# nixiRemoteControlReceiver.net
KiCad netlist of a schematic drawn in EAGLE
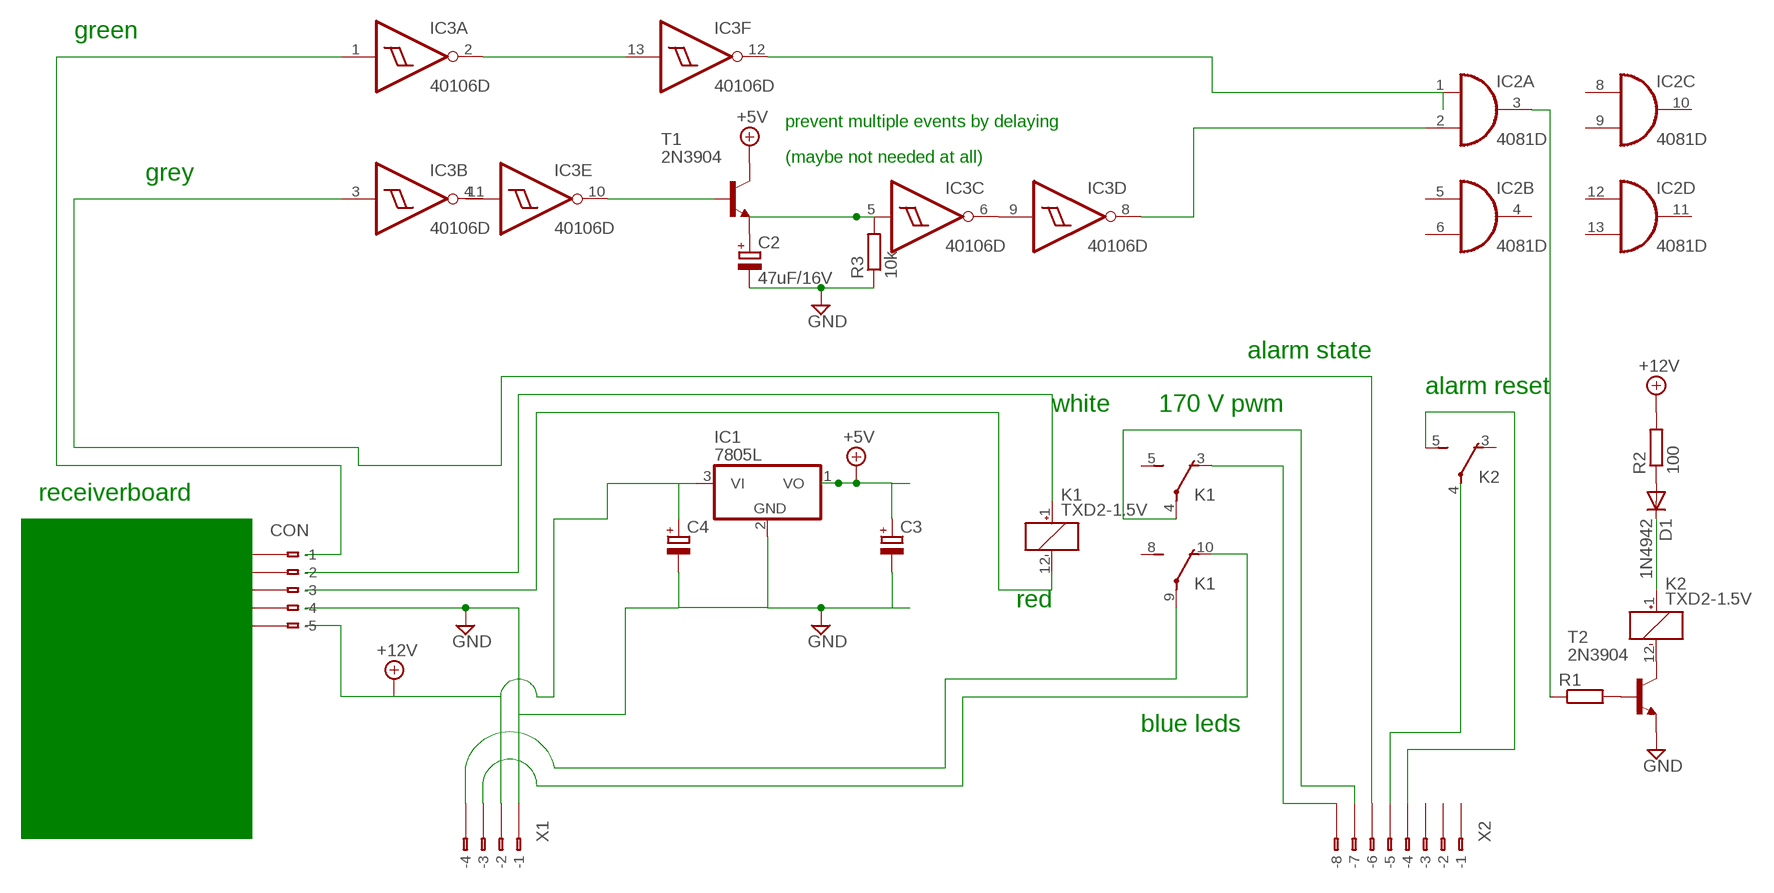
[diagram p0: schematic, sheet 1]

(export (version "E")
  (design (tool "Eeschema 10.0.6"))
  (components
    (comp (ref "C2")
      (value "47uF/16V")
      (footprint "eagle-import:EB20D")
      (libsource (lib "eagle-import") (part "CPOL-EUE10-20"))
    )
    (comp (ref "C3")
      (value "CPOL-EUE10-20")
      (footprint "eagle-import:EB20D")
      (libsource (lib "eagle-import") (part "CPOL-EUE10-20"))
    )
    (comp (ref "C4")
      (value "CPOL-EUE10-20")
      (footprint "eagle-import:EB20D")
      (libsource (lib "eagle-import") (part "CPOL-EUE10-20"))
    )
    (comp (ref "CON")
      (value "233-105")
      (footprint "eagle-import:233-105")
      (libsource (lib "eagle-import") (part "233-105"))
    )
    (comp (ref "D1")
      (value "1N4942")
      (footprint "eagle-import:DO41-10")
      (libsource (lib "eagle-import") (part "1N4942"))
    )
    (comp (ref "IC1")
      (value "7805L")
      (footprint "eagle-import:TO92")
      (libsource (lib "eagle-import") (part "78L05"))
    )
    (comp (ref "IC2")
      (value "4081D")
      (footprint "eagle-import:SO14")
      (libsource (lib "eagle-import") (part "4081D"))
    )
    (comp (ref "IC3")
      (value "40106D")
      (footprint "eagle-import:SO14")
      (libsource (lib "eagle-import") (part "40106D"))
    )
    (comp (ref "K1")
      (value "TXD2-1.5V")
      (footprint "eagle-import:TXD2")
      (libsource (lib "eagle-import") (part "TX?-D21.5V"))
    )
    (comp (ref "K2")
      (value "TXD2-1.5V")
      (footprint "eagle-import:TXD2")
      (libsource (lib "eagle-import") (part "TX?-D21.5V"))
    )
    (comp (ref "R1")
      (value "R-EU_0411/15")
      (footprint "eagle-import:0411_15")
      (libsource (lib "eagle-import") (part "R-EU_0411/15"))
    )
    (comp (ref "R2")
      (value "100")
      (footprint "eagle-import:0411_15")
      (libsource (lib "eagle-import") (part "R-EU_0411/15"))
    )
    (comp (ref "R3")
      (value "10k")
      (footprint "eagle-import:0411_15")
      (libsource (lib "eagle-import") (part "R-EU_0411/15"))
    )
    (comp (ref "T1")
      (value "2N3904")
      (footprint "eagle-import:TO92")
      (libsource (lib "eagle-import") (part "2N3904"))
    )
    (comp (ref "T2")
      (value "2N3904")
      (footprint "eagle-import:TO92")
      (libsource (lib "eagle-import") (part "2N3904"))
    )
    (comp (ref "X1")
      (value "233-104")
      (footprint "eagle-import:233-104")
      (libsource (lib "eagle-import") (part "233-104"))
    )
    (comp (ref "X2")
      (value "233-108")
      (footprint "eagle-import:233-108")
      (libsource (lib "eagle-import") (part "233-108"))
    )
  )
  (nets
    (net (code "1") (name "+5V") (class "Default")
      (node (ref "C3") (pin "+") (pinfunction "+_+") (pintype "passive"))
      (node (ref "IC1") (pin "1") (pinfunction "VO_1") (pintype "passive"))
      (node (ref "T1") (pin "1") (pinfunction "C_1") (pintype "passive"))
    )
    (net (code "2") (name "+12V") (class "Default")
      (node (ref "C4") (pin "+") (pinfunction "+_+") (pintype "passive"))
      (node (ref "IC1") (pin "3") (pinfunction "VI_3") (pintype "input"))
      (node (ref "R2") (pin "2") (pinfunction "2_2") (pintype "passive"))
      (node (ref "X1") (pin "B2") (pinfunction "B-2_B2") (pintype "passive"))
    )
    (net (code "3") (name "GND") (class "Default")
      (node (ref "C2") (pin "-") (pinfunction "-_-") (pintype "passive"))
      (node (ref "C3") (pin "-") (pinfunction "-_-") (pintype "passive"))
      (node (ref "C4") (pin "-") (pinfunction "-_-") (pintype "passive"))
      (node (ref "IC1") (pin "2") (pinfunction "GND_2") (pintype "passive"))
      (node (ref "R3") (pin "1") (pinfunction "1_1") (pintype "passive"))
      (node (ref "T2") (pin "3") (pinfunction "E_3") (pintype "passive"))
      (node (ref "X1") (pin "B1") (pinfunction "B-1_B1") (pintype "passive"))
    )
    (net (code "4") (name "Net-(D1-PadA)") (class "Default")
      (node (ref "D1") (pin "A") (pinfunction "A_A") (pintype "passive"))
      (node (ref "R2") (pin "1") (pinfunction "1_1") (pintype "passive"))
    )
    (net (code "5") (name "Net-(IC2A-I1)") (class "Default")
      (node (ref "IC2") (pin "2") (pinfunction "I1_2") (pintype "input"))
      (node (ref "IC3") (pin "8") (pinfunction "O_8") (pintype "output"))
    )
    (net (code "6") (name "Net-(IC2A-O)") (class "Default")
      (node (ref "IC2") (pin "3") (pinfunction "O_3") (pintype "output"))
      (node (ref "R1") (pin "1") (pinfunction "1_1") (pintype "passive"))
    )
    (net (code "7") (name "Net-(IC3A-O)") (class "Default")
      (node (ref "IC3") (pin "13") (pinfunction "I_13") (pintype "input"))
      (node (ref "IC3") (pin "2") (pinfunction "O_2") (pintype "output"))
    )
    (net (code "8") (name "Net-(IC3B-I)") (class "Default")
      (node (ref "IC3") (pin "3") (pinfunction "I_3") (pintype "input"))
      (node (ref "X2") (pin "B6") (pinfunction "B-6_B6") (pintype "passive"))
    )
    (net (code "9") (name "Net-(IC3C-I)") (class "Default")
      (node (ref "IC3") (pin "5") (pinfunction "I_5") (pintype "input"))
      (node (ref "R3") (pin "2") (pinfunction "2_2") (pintype "passive"))
    )
    (net (code "10") (name "Net-(IC3C-O)") (class "Default")
      (node (ref "IC3") (pin "6") (pinfunction "O_6") (pintype "output"))
      (node (ref "IC3") (pin "9") (pinfunction "I_9") (pintype "input"))
    )
    (net (code "11") (name "Net-(IC3E-O)") (class "Default")
      (node (ref "IC3") (pin "10") (pinfunction "O_10") (pintype "output"))
      (node (ref "T1") (pin "2") (pinfunction "B_2") (pintype "passive"))
    )
    (net (code "12") (name "Net-(K1A-O)") (class "Default")
      (node (ref "K1") (pin "3") (pinfunction "O_3") (pintype "passive"))
      (node (ref "X2") (pin "B8") (pinfunction "B-8_B8") (pintype "passive"))
    )
    (net (code "13") (name "Net-(K1A-P)") (class "Default")
      (node (ref "K1") (pin "4") (pinfunction "P_4") (pintype "passive"))
      (node (ref "X2") (pin "B7") (pinfunction "B-7_B7") (pintype "passive"))
    )
    (net (code "14") (name "Net-(K1B-O)") (class "Default")
      (node (ref "K1") (pin "10") (pinfunction "O_10") (pintype "passive"))
      (node (ref "X1") (pin "B3") (pinfunction "B-3_B3") (pintype "passive"))
    )
    (net (code "15") (name "Net-(K1B-P)") (class "Default")
      (node (ref "K1") (pin "9") (pinfunction "P_9") (pintype "passive"))
      (node (ref "X1") (pin "B4") (pinfunction "B-4_B4") (pintype "passive"))
    )
    (net (code "16") (name "Net-(K2A-S)") (class "Default")
      (node (ref "K2") (pin "5") (pinfunction "S_5") (pintype "passive"))
      (node (ref "X2") (pin "B4") (pinfunction "B-4_B4") (pintype "passive"))
    )
    (net (code "17") (name "Net-(K2C-+)") (class "Default")
      (node (ref "D1") (pin "C") (pinfunction "C_C") (pintype "passive"))
      (node (ref "K2") (pin "1") (pinfunction "+_1") (pintype "passive"))
    )
    (net (code "18") (name "Net-(K2C--)") (class "Default")
      (node (ref "K2") (pin "12") (pinfunction "-_12") (pintype "passive"))
      (node (ref "T2") (pin "1") (pinfunction "C_1") (pintype "passive"))
    )
    (net (code "19") (name "Net-(T1-E)") (class "Default")
      (node (ref "C2") (pin "+") (pinfunction "+_+") (pintype "passive"))
      (node (ref "T1") (pin "3") (pinfunction "E_3") (pintype "passive"))
    )
    (net (code "20") (name "Net-(T2-B)") (class "Default")
      (node (ref "R1") (pin "2") (pinfunction "2_2") (pintype "passive"))
      (node (ref "T2") (pin "2") (pinfunction "B_2") (pintype "passive"))
    )
    (net (code "21") (name "unconnected-(CON--1-PadA1)") (class "Default")
      (node (ref "CON") (pin "A1") (pinfunction "-1_A1") (pintype "passive"))
    )
    (net (code "22") (name "unconnected-(CON--2-PadA2)") (class "Default")
      (node (ref "CON") (pin "A2") (pinfunction "-2_A2") (pintype "passive"))
    )
    (net (code "23") (name "unconnected-(CON--3-PadA3)") (class "Default")
      (node (ref "CON") (pin "A3") (pinfunction "-3_A3") (pintype "passive"))
    )
    (net (code "24") (name "unconnected-(CON--4-PadA4)") (class "Default")
      (node (ref "CON") (pin "A4") (pinfunction "-4_A4") (pintype "passive"))
    )
    (net (code "25") (name "unconnected-(CON--5-PadA5)") (class "Default")
      (node (ref "CON") (pin "A5") (pinfunction "-5_A5") (pintype "passive"))
    )
    (net (code "26") (name "unconnected-(CON-B-1-PadB1)") (class "Default")
      (node (ref "CON") (pin "B1") (pinfunction "B-1_B1") (pintype "passive"))
    )
    (net (code "27") (name "unconnected-(CON-B-2-PadB2)") (class "Default")
      (node (ref "CON") (pin "B2") (pinfunction "B-2_B2") (pintype "passive"))
    )
    (net (code "28") (name "unconnected-(CON-B-3-PadB3)") (class "Default")
      (node (ref "CON") (pin "B3") (pinfunction "B-3_B3") (pintype "passive"))
    )
    (net (code "29") (name "unconnected-(CON-B-4-PadB4)") (class "Default")
      (node (ref "CON") (pin "B4") (pinfunction "B-4_B4") (pintype "passive"))
    )
    (net (code "30") (name "unconnected-(CON-B-5-PadB5)") (class "Default")
      (node (ref "CON") (pin "B5") (pinfunction "B-5_B5") (pintype "passive"))
    )
    (net (code "31") (name "unconnected-(IC2A-I0-Pad1)") (class "Default")
      (node (ref "IC2") (pin "1") (pinfunction "I0_1") (pintype "input"))
    )
    (net (code "32") (name "unconnected-(IC2B-I0-Pad5)") (class "Default")
      (node (ref "IC2") (pin "5") (pinfunction "I0_5") (pintype "input"))
    )
    (net (code "33") (name "unconnected-(IC2B-I1-Pad6)") (class "Default")
      (node (ref "IC2") (pin "6") (pinfunction "I1_6") (pintype "input"))
    )
    (net (code "34") (name "unconnected-(IC2B-O-Pad4)") (class "Default")
      (node (ref "IC2") (pin "4") (pinfunction "O_4") (pintype "output"))
    )
    (net (code "35") (name "unconnected-(IC2C-I0-Pad8)") (class "Default")
      (node (ref "IC2") (pin "8") (pinfunction "I0_8") (pintype "input"))
    )
    (net (code "36") (name "unconnected-(IC2C-I1-Pad9)") (class "Default")
      (node (ref "IC2") (pin "9") (pinfunction "I1_9") (pintype "input"))
    )
    (net (code "37") (name "unconnected-(IC2C-O-Pad10)") (class "Default")
      (node (ref "IC2") (pin "10") (pinfunction "O_10") (pintype "output"))
    )
    (net (code "38") (name "unconnected-(IC2D-I0-Pad12)") (class "Default")
      (node (ref "IC2") (pin "12") (pinfunction "I0_12") (pintype "input"))
    )
    (net (code "39") (name "unconnected-(IC2D-I1-Pad13)") (class "Default")
      (node (ref "IC2") (pin "13") (pinfunction "I1_13") (pintype "input"))
    )
    (net (code "40") (name "unconnected-(IC2D-O-Pad11)") (class "Default")
      (node (ref "IC2") (pin "11") (pinfunction "O_11") (pintype "output"))
    )
    (net (code "41") (name "unconnected-(IC3A-I-Pad1)") (class "Default")
      (node (ref "IC3") (pin "1") (pinfunction "I_1") (pintype "input"))
    )
    (net (code "42") (name "unconnected-(IC3B-O-Pad4)") (class "Default")
      (node (ref "IC3") (pin "4") (pinfunction "O_4") (pintype "output"))
    )
    (net (code "43") (name "unconnected-(IC3E-I-Pad11)") (class "Default")
      (node (ref "IC3") (pin "11") (pinfunction "I_11") (pintype "input"))
    )
    (net (code "44") (name "unconnected-(IC3F-O-Pad12)") (class "Default")
      (node (ref "IC3") (pin "12") (pinfunction "O_12") (pintype "output"))
    )
    (net (code "45") (name "unconnected-(K1A-S-Pad5)") (class "Default")
      (node (ref "K1") (pin "5") (pinfunction "S_5") (pintype "passive"))
    )
    (net (code "46") (name "unconnected-(K1B-S-Pad8)") (class "Default")
      (node (ref "K1") (pin "8") (pinfunction "S_8") (pintype "passive"))
    )
    (net (code "47") (name "unconnected-(K1C-+-Pad1)") (class "Default")
      (node (ref "K1") (pin "1") (pinfunction "+_1") (pintype "passive"))
    )
    (net (code "48") (name "unconnected-(K1C---Pad12)") (class "Default")
      (node (ref "K1") (pin "12") (pinfunction "-_12") (pintype "passive"))
    )
    (net (code "49") (name "unconnected-(K2A-O-Pad3)") (class "Default")
      (node (ref "K2") (pin "3") (pinfunction "O_3") (pintype "passive"))
    )
    (net (code "50") (name "unconnected-(K2A-P-Pad4)") (class "Default")
      (node (ref "K2") (pin "4") (pinfunction "P_4") (pintype "passive"))
    )
    (net (code "51") (name "unconnected-(X1--1-PadA1)") (class "Default")
      (node (ref "X1") (pin "A1") (pinfunction "-1_A1") (pintype "passive"))
    )
    (net (code "52") (name "unconnected-(X1--2-PadA2)") (class "Default")
      (node (ref "X1") (pin "A2") (pinfunction "-2_A2") (pintype "passive"))
    )
    (net (code "53") (name "unconnected-(X1--3-PadA3)") (class "Default")
      (node (ref "X1") (pin "A3") (pinfunction "-3_A3") (pintype "passive"))
    )
    (net (code "54") (name "unconnected-(X1--4-PadA4)") (class "Default")
      (node (ref "X1") (pin "A4") (pinfunction "-4_A4") (pintype "passive"))
    )
    (net (code "55") (name "unconnected-(X2--1-PadA1)") (class "Default")
      (node (ref "X2") (pin "A1") (pinfunction "-1_A1") (pintype "passive"))
    )
    (net (code "56") (name "unconnected-(X2--2-PadA2)") (class "Default")
      (node (ref "X2") (pin "A2") (pinfunction "-2_A2") (pintype "passive"))
    )
    (net (code "57") (name "unconnected-(X2--3-PadA3)") (class "Default")
      (node (ref "X2") (pin "A3") (pinfunction "-3_A3") (pintype "passive"))
    )
    (net (code "58") (name "unconnected-(X2--4-PadA4)") (class "Default")
      (node (ref "X2") (pin "A4") (pinfunction "-4_A4") (pintype "passive"))
    )
    (net (code "59") (name "unconnected-(X2--5-PadA5)") (class "Default")
      (node (ref "X2") (pin "A5") (pinfunction "-5_A5") (pintype "passive"))
    )
    (net (code "60") (name "unconnected-(X2--6-PadA6)") (class "Default")
      (node (ref "X2") (pin "A6") (pinfunction "-6_A6") (pintype "passive"))
    )
    (net (code "61") (name "unconnected-(X2--7-PadA7)") (class "Default")
      (node (ref "X2") (pin "A7") (pinfunction "-7_A7") (pintype "passive"))
    )
    (net (code "62") (name "unconnected-(X2--8-PadA8)") (class "Default")
      (node (ref "X2") (pin "A8") (pinfunction "-8_A8") (pintype "passive"))
    )
    (net (code "63") (name "unconnected-(X2-B-1-PadB1)") (class "Default")
      (node (ref "X2") (pin "B1") (pinfunction "B-1_B1") (pintype "passive"))
    )
    (net (code "64") (name "unconnected-(X2-B-2-PadB2)") (class "Default")
      (node (ref "X2") (pin "B2") (pinfunction "B-2_B2") (pintype "passive"))
    )
    (net (code "65") (name "unconnected-(X2-B-3-PadB3)") (class "Default")
      (node (ref "X2") (pin "B3") (pinfunction "B-3_B3") (pintype "passive"))
    )
    (net (code "66") (name "unconnected-(X2-B-5-PadB5)") (class "Default")
      (node (ref "X2") (pin "B5") (pinfunction "B-5_B5") (pintype "passive"))
    )
  )
)
